# V1_0.net
KiCad netlist of a schematic drawn in Altium Designer
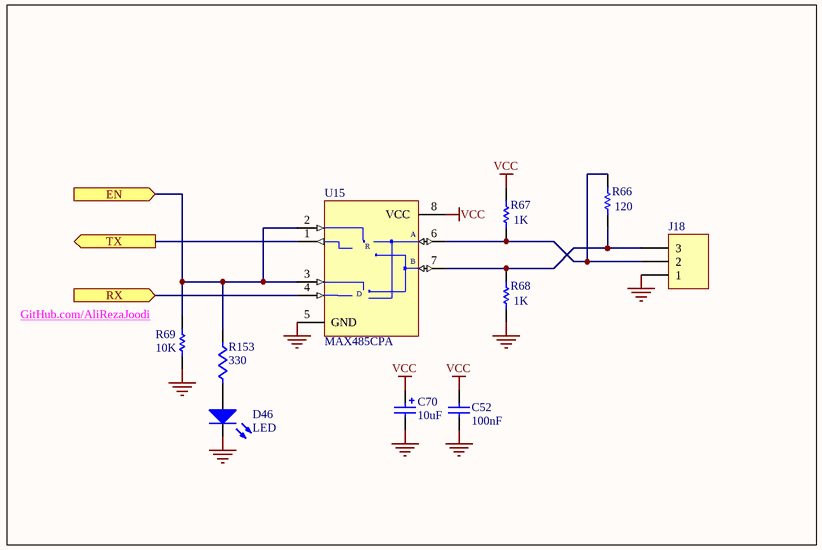
[diagram p0: V1.0.SchDoc]

(export (version "E")
  (design (tool "Eeschema 10.0.6"))
  (components
    (comp (ref "C52")
      (value "100nF")
      (footprint "0805")
      (description "Capacitor")
      (fields
        (field (name "MANUFACTURER") "Generic Components")
        (field (name "Comment") "Cap")
        (field (name "PUBLISHER") "Altium Limited")
      )
      (libsource (lib "Miscellaneous Devices") (part "Cap"))
    )
    (comp (ref "C70")
      (value "10uF")
      (footprint "Cap_B")
      (description "Polarized Capacitor (Radial)")
      (fields
        (field (name "MANUFACTURER") "Generic Components")
        (field (name "Comment") "Capacitor")
        (field (name "PUBLISHER") "Altium Limited")
      )
      (libsource (lib "Miscellaneous Devices") (part "Cap Pol1"))
    )
    (comp (ref "D46")
      (value "LED")
      (footprint "0805_Diode")
      (description "Typical INFRARED GaAs LED")
      (fields (field (name "MANUFACTURER") "Generic Components") (field (name "PUBLISHER") "Altium Limited"))
      (libsource (lib "Miscellaneous Devices") (part "LED"))
    )
    (comp (ref "J18")
      (value "Header 3")
      (footprint "Fonics_3PIN_1")
      (description "Header, 3-Pin")
      (fields (field (name "MANUFACTURER") "Generic Components") (field (name "PUBLISHER") "Altium Limited"))
      (libsource (lib "Miscellaneous Connectors") (part "Header 3"))
    )
    (comp (ref "R66")
      (value "120")
      (footprint "RESC3216N")
      (description "Resistor")
      (fields (field (name "Comment") "Res1") (field (name "PUBLISHER") "Altium Limited"))
      (libsource (lib "Miscellaneous Devices") (part "Res1"))
    )
    (comp (ref "R67")
      (value "1K")
      (footprint "0805")
      (description "Resistor")
      (fields (field (name "Comment") "Res1") (field (name "PUBLISHER") "Altium Limited"))
      (libsource (lib "Miscellaneous Devices") (part "Res1"))
    )
    (comp (ref "R68")
      (value "1K")
      (footprint "0805")
      (description "Resistor")
      (fields (field (name "Comment") "Res1") (field (name "PUBLISHER") "Altium Limited"))
      (libsource (lib "Miscellaneous Devices") (part "Res1"))
    )
    (comp (ref "R69")
      (value "10K")
      (footprint "0805")
      (description "Resistor")
      (fields (field (name "Comment") "Res1") (field (name "PUBLISHER") "Altium Limited"))
      (libsource (lib "Miscellaneous Devices") (part "Res1"))
    )
    (comp (ref "R153")
      (value "330")
      (footprint "0805")
      (description "Resistor")
      (fields
        (field (name "MANUFACTURER") "Generic Components")
        (field (name "Comment") "Res1")
        (field (name "PUBLISHER") "Altium Limited")
      )
      (libsource (lib "") (part "Res1_1"))
    )
    (comp (ref "U15")
      (value "MAX485CPA")
      (footprint "SOP127P636-8N")
      (description "Low-Power, Slew-Rate-Limited RS-485/RS-422 Transceiver")
      (fields (field (name "PUBLISHER") "Altium Limited"))
      (libsource (lib "Maxim Communication Transceiver") (part "MAX485CPA"))
    )
  )
  (nets
    (net (code "1") (name "/EN") (class "Default")
      (node (ref "R153") (pin "1") (pinfunction "1_1") (pintype "passive"))
      (node (ref "R69") (pin "2") (pinfunction "2_2") (pintype "passive"))
      (node (ref "U15") (pin "2") (pinfunction "~{RE}_2") (pintype "input"))
      (node (ref "U15") (pin "3") (pinfunction "DE_3") (pintype "input"))
    )
    (net (code "2") (name "/RX") (class "Default")
      (node (ref "U15") (pin "4") (pinfunction "DI_4") (pintype "input"))
    )
    (net (code "3") (name "/TX") (class "Default")
      (node (ref "U15") (pin "1") (pinfunction "RO_1") (pintype "output"))
    )
    (net (code "4") (name "GND") (class "Default")
      (node (ref "C52") (pin "1") (pinfunction "1_1") (pintype "passive"))
      (node (ref "C70") (pin "2") (pinfunction "2_2") (pintype "passive"))
      (node (ref "D46") (pin "2") (pinfunction "K_2") (pintype "passive"))
      (node (ref "J18") (pin "1") (pinfunction "1_1") (pintype "passive"))
      (node (ref "R68") (pin "2") (pinfunction "2_2") (pintype "passive"))
      (node (ref "R69") (pin "1") (pinfunction "1_1") (pintype "passive"))
      (node (ref "U15") (pin "5") (pinfunction "GND_5") (pintype "power_in"))
    )
    (net (code "5") (name "Net-(D46-A)") (class "Default")
      (node (ref "D46") (pin "1") (pinfunction "A_1") (pintype "passive"))
      (node (ref "R153") (pin "2") (pinfunction "2_2") (pintype "passive"))
    )
    (net (code "6") (name "Net-(U15-A)") (class "Default")
      (node (ref "J18") (pin "2") (pinfunction "2_2") (pintype "passive"))
      (node (ref "R66") (pin "1") (pinfunction "1_1") (pintype "passive"))
      (node (ref "R67") (pin "2") (pinfunction "2_2") (pintype "passive"))
      (node (ref "U15") (pin "6") (pinfunction "A_6") (pintype "bidirectional"))
    )
    (net (code "7") (name "Net-(U15-B)") (class "Default")
      (node (ref "J18") (pin "3") (pinfunction "3_3") (pintype "passive"))
      (node (ref "R66") (pin "2") (pinfunction "2_2") (pintype "passive"))
      (node (ref "R68") (pin "1") (pinfunction "1_1") (pintype "passive"))
      (node (ref "U15") (pin "7") (pinfunction "B_7") (pintype "bidirectional"))
    )
    (net (code "8") (name "VCC") (class "Default")
      (node (ref "C52") (pin "2") (pinfunction "2_2") (pintype "passive"))
      (node (ref "C70") (pin "1") (pinfunction "1_1") (pintype "passive"))
      (node (ref "R67") (pin "1") (pinfunction "1_1") (pintype "passive"))
      (node (ref "U15") (pin "8") (pinfunction "VCC_8") (pintype "power_in"))
    )
  )
)
